# MCPS_Power_030307.net
KiCad netlist of a schematic drawn in Altium Designer
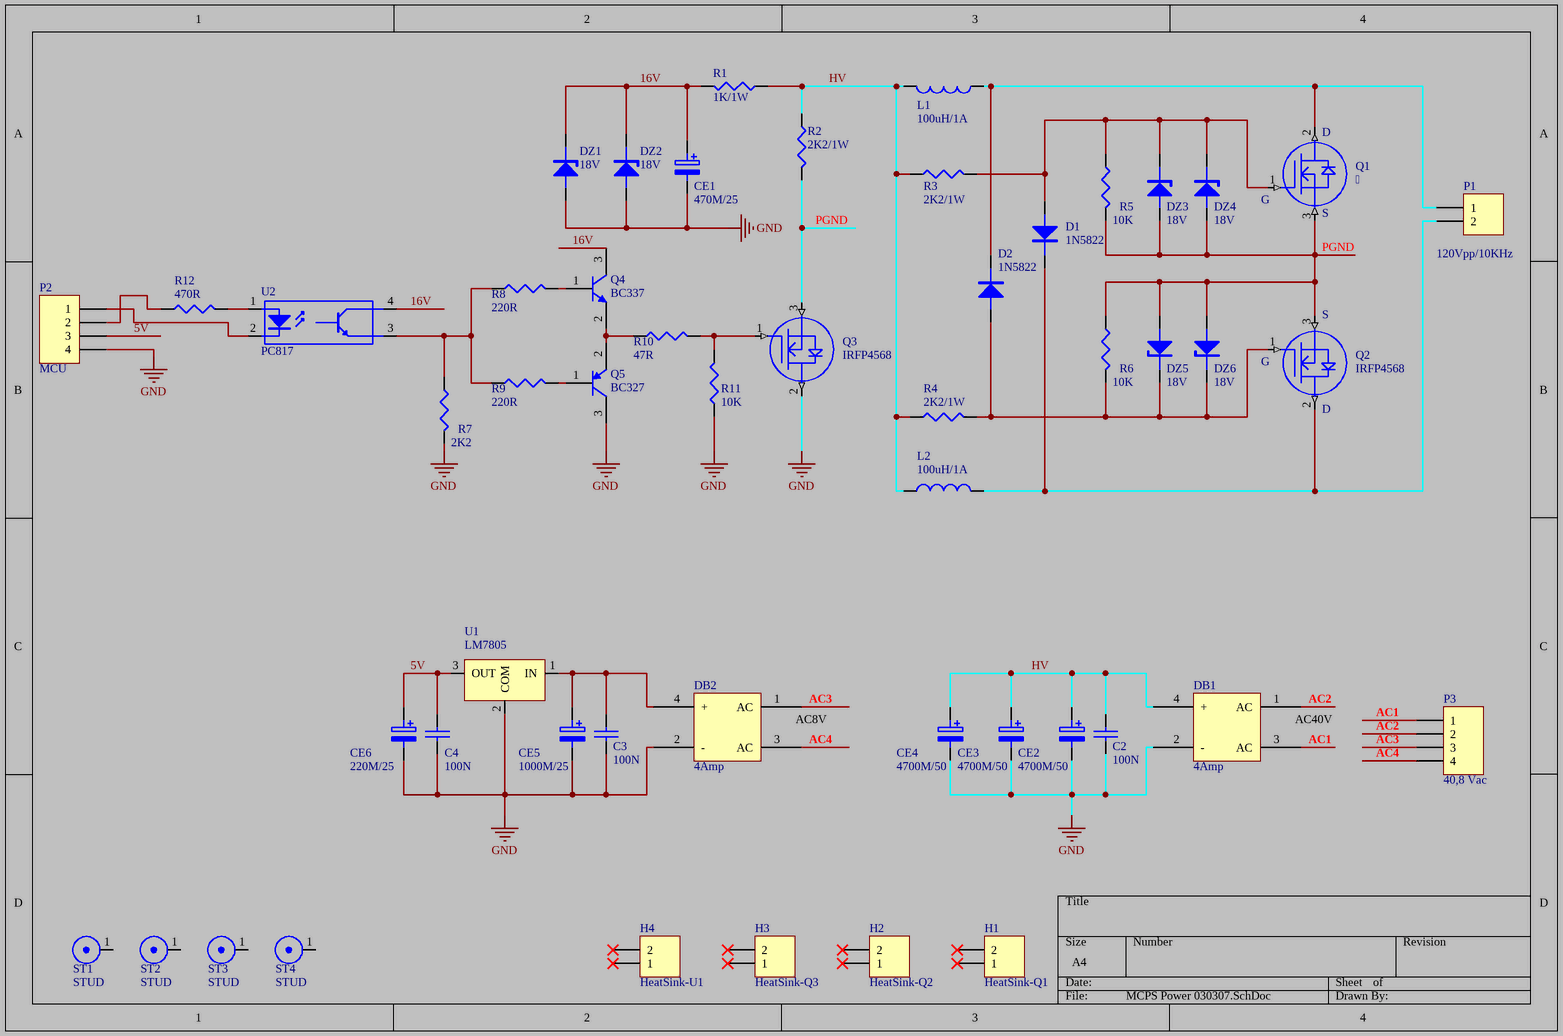
[diagram p0: MCPS Power 030307.SchDoc]

(export (version "E")
  (design (tool "Eeschema 10.0.6"))
  (components
    (comp (ref "C2") (value "100N") (footprint "c2P") (libsource (lib "*") (part "C")))
    (comp (ref "C3") (value "100N") (footprint "c2P") (libsource (lib "*") (part "C")))
    (comp (ref "C4") (value "100N") (footprint "c2P") (libsource (lib "*") (part "C")))
    (comp (ref "CE1") (value "470M/25") (footprint "cap2p12") (libsource (lib "*") (part "E")))
    (comp (ref "CE2") (value "4700M/50") (footprint "CAP3P5") (libsource (lib "*") (part "E")))
    (comp (ref "CE3") (value "4700M/50") (footprint "CAP3P5") (libsource (lib "*") (part "E")))
    (comp (ref "CE4") (value "4700M/50") (footprint "CAP3P5") (libsource (lib "*") (part "E")))
    (comp (ref "CE5") (value "1000M/25") (footprint "cap2p12") (libsource (lib "*") (part "E")))
    (comp (ref "CE6") (value "220M/25") (footprint "cap2p12") (libsource (lib "*") (part "E")))
    (comp (ref "D1") (value "1N5822") (footprint "D54") (libsource (lib "MyAltiumLib9702") (part "D")))
    (comp (ref "D2") (value "1N5822") (footprint "D54") (libsource (lib "MyAltiumLib9702") (part "D")))
    (comp (ref "DB1")
      (value "4Amp")
      (footprint "BRG GBU")
      (libsource (lib "1402 Schlib 2020") (part "BRIDGE"))
    )
    (comp (ref "DB2") (value "4Amp") (footprint "BRG F") (libsource (lib "1402 Schlib 2020") (part "BRIDGE")))
    (comp (ref "DZ1") (value "18V") (footprint "D4P") (libsource (lib "MyAltiumLib9702") (part "DZ")))
    (comp (ref "DZ2") (value "18V") (footprint "D4P") (libsource (lib "MyAltiumLib9702") (part "DZ")))
    (comp (ref "DZ3") (value "18V") (footprint "D4P") (libsource (lib "MyAltiumLib9702") (part "DZ")))
    (comp (ref "DZ4") (value "18V") (footprint "D4P") (libsource (lib "MyAltiumLib9702") (part "DZ")))
    (comp (ref "DZ5") (value "18V") (footprint "D4P") (libsource (lib "MyAltiumLib9702") (part "DZ")))
    (comp (ref "DZ6") (value "18V") (footprint "D4P") (libsource (lib "MyAltiumLib9702") (part "DZ")))
    (comp (ref "H1")
      (value "HeatSink-Q1")
      (footprint "heatsink2")
      (description "Header, 2-Pin")
      (fields (field (name "PUBLISHER") "Altium Limited"))
      (libsource (lib "") (part "Header 2_1"))
    )
    (comp (ref "H2")
      (value "HeatSink-Q2")
      (footprint "heatsink2")
      (description "Header, 2-Pin")
      (fields (field (name "PUBLISHER") "Altium Limited"))
      (libsource (lib "") (part "Header 2_1"))
    )
    (comp (ref "H3")
      (value "HeatSink-Q3")
      (footprint "heatsink2")
      (description "Header, 2-Pin")
      (fields (field (name "PUBLISHER") "Altium Limited"))
      (libsource (lib "") (part "Header 2_1"))
    )
    (comp (ref "H4")
      (value "HeatSink-U1")
      (footprint "heatsink5")
      (description "Header, 2-Pin")
      (fields (field (name "PUBLISHER") "Altium Limited"))
      (libsource (lib "") (part "Header 2_1"))
    )
    (comp (ref "L1")
      (value "100uH/1A")
      (footprint "Inductor-Brown")
      (libsource (lib "MyAltiumLib9702") (part "INDUCTOR"))
    )
    (comp (ref "L2") (value "100uH/1A") (footprint "Inductor-Brown") (libsource (lib "") (part "INDUCTOR_1")))
    (comp (ref "P1")
      (value "120Vpp/10KHz")
      (footprint "2EDG")
      (description "Header, 2-Pin")
      (fields (field (name "PUBLISHER") "Altium Limited"))
      (libsource (lib "Miscellaneous Connectors") (part "Header 2"))
    )
    (comp (ref "P2")
      (value "MCU")
      (footprint "DSIP4")
      (description "Header, 4-Pin")
      (fields (field (name "PUBLISHER") "Altium Limited"))
      (libsource (lib "Miscellaneous Connectors") (part "Header 4"))
    )
    (comp (ref "P3")
      (value "40,8 Vac")
      (footprint "4EDG")
      (description "Header, 4-Pin")
      (fields (field (name "PUBLISHER") "Altium Limited"))
      (libsource (lib "") (part "Header 4_1"))
    )
    (comp (ref "Q1") (value "") (footprint "TO220T") (libsource (lib "1402 Schlib 2020") (part "MOSFET N")))
    (comp (ref "Q2")
      (value "IRFP4568")
      (footprint "TO220T")
      (libsource (lib "1402 Schlib 2020") (part "MOSFET N"))
    )
    (comp (ref "Q3")
      (value "IRFP4568")
      (footprint "TO220T")
      (libsource (lib "1402 Schlib 2020") (part "MOSFET N"))
    )
    (comp (ref "Q4")
      (value "BC337")
      (footprint "CBE-BC546")
      (libsource (lib "1402 Schlib 2020") (part "BC546"))
    )
    (comp (ref "Q5")
      (value "BC327")
      (footprint "CBE-BC546")
      (description "PNP")
      (fields (field (name "PUBLISHER") "Altium Limited"))
      (libsource (lib "1402 Schlib 2020") (part "M6"))
    )
    (comp (ref "R1") (value "1K/1W") (footprint "w1") (libsource (lib "*") (part "R")))
    (comp (ref "R2") (value "2K2/1W") (footprint "w1") (libsource (lib "*") (part "R")))
    (comp (ref "R3") (value "2K2/1W") (footprint "w1") (libsource (lib "*") (part "R")))
    (comp (ref "R4") (value "2K2/1W") (footprint "w1") (libsource (lib "*") (part "R")))
    (comp (ref "R5") (value "10K") (footprint "R5P") (libsource (lib "*") (part "R")))
    (comp (ref "R6") (value "10K") (footprint "R5P") (libsource (lib "*") (part "R")))
    (comp (ref "R7") (value "2K2") (footprint "R4P") (libsource (lib "*") (part "R")))
    (comp (ref "R8") (value "220R") (footprint "R4P") (libsource (lib "*") (part "R")))
    (comp (ref "R9") (value "220R") (footprint "R4P") (libsource (lib "*") (part "R")))
    (comp (ref "R10") (value "47R") (footprint "R4P") (libsource (lib "*") (part "R")))
    (comp (ref "R11") (value "10K") (footprint "R4P") (libsource (lib "*") (part "R")))
    (comp (ref "R12") (value "470R") (footprint "R4P") (libsource (lib "*") (part "R")))
    (comp (ref "ST1") (value "STUD") (footprint "CORNER") (libsource (lib "1402 Schlib 2020") (part "STUD")))
    (comp (ref "ST2") (value "STUD") (footprint "CORNER") (libsource (lib "1402 Schlib 2020") (part "STUD")))
    (comp (ref "ST3") (value "STUD") (footprint "CORNER") (libsource (lib "1402 Schlib 2020") (part "STUD")))
    (comp (ref "ST4") (value "STUD") (footprint "CORNER") (libsource (lib "1402 Schlib 2020") (part "STUD")))
    (comp (ref "U1")
      (value "LM7805")
      (footprint "TO220T")
      (description "SMD")
      (libsource (lib "1402 Schlib 2020") (part "Regulator"))
    )
    (comp (ref "U2")
      (value "PC817")
      (footprint "DIP4")
      (libsource (lib "1402 Schlib 2020") (part "OPTODIP4"))
    )
  )
  (nets
    (net (code "1") (name "/5V") (class "Default")
      (node (ref "C4") (pin "1") (pintype "passive"))
      (node (ref "CE6") (pin "1") (pintype "passive"))
      (node (ref "P2") (pin "3") (pinfunction "3_3") (pintype "passive"))
      (node (ref "U1") (pin "3") (pinfunction "OUT_3") (pintype "passive"))
    )
    (net (code "2") (name "/16V") (class "Default")
      (node (ref "CE1") (pin "1") (pintype "passive"))
      (node (ref "DZ1") (pin "2") (pinfunction "K_2") (pintype "passive"))
      (node (ref "DZ2") (pin "2") (pinfunction "K_2") (pintype "passive"))
      (node (ref "Q4") (pin "3") (pinfunction "C_3") (pintype "passive"))
      (node (ref "R1") (pin "2") (pintype "passive"))
      (node (ref "U2") (pin "4") (pinfunction "C_4") (pintype "passive"))
    )
    (net (code "3") (name "/AC1") (class "Default")
      (node (ref "DB1") (pin "3") (pinfunction "AC_3") (pintype "passive"))
      (node (ref "P3") (pin "1") (pinfunction "1_1") (pintype "passive"))
    )
    (net (code "4") (name "/AC2") (class "Default")
      (node (ref "DB1") (pin "1") (pinfunction "AC_1") (pintype "passive"))
      (node (ref "P3") (pin "2") (pinfunction "2_2") (pintype "passive"))
    )
    (net (code "5") (name "/AC3") (class "Default")
      (node (ref "DB2") (pin "1") (pinfunction "AC_1") (pintype "passive"))
      (node (ref "P3") (pin "3") (pinfunction "3_3") (pintype "passive"))
    )
    (net (code "6") (name "/AC4") (class "Default")
      (node (ref "DB2") (pin "3") (pinfunction "AC_3") (pintype "passive"))
      (node (ref "P3") (pin "4") (pinfunction "4_4") (pintype "passive"))
    )
    (net (code "7") (name "/HV") (class "Default")
      (node (ref "C2") (pin "1") (pintype "passive"))
      (node (ref "CE2") (pin "1") (pintype "passive"))
      (node (ref "CE3") (pin "1") (pintype "passive"))
      (node (ref "CE4") (pin "1") (pintype "passive"))
      (node (ref "DB1") (pin "4") (pinfunction "+_4") (pintype "passive"))
      (node (ref "L1") (pin "1") (pinfunction "1_1") (pintype "passive"))
      (node (ref "L2") (pin "1") (pinfunction "1_1") (pintype "passive"))
      (node (ref "R1") (pin "1") (pintype "passive"))
      (node (ref "R2") (pin "1") (pintype "passive"))
      (node (ref "R3") (pin "1") (pintype "passive"))
      (node (ref "R4") (pin "1") (pintype "passive"))
    )
    (net (code "8") (name "/PGND") (class "Default")
      (node (ref "DZ3") (pin "1") (pinfunction "A_1") (pintype "passive"))
      (node (ref "DZ4") (pin "1") (pinfunction "A_1") (pintype "passive"))
      (node (ref "DZ5") (pin "1") (pinfunction "A_1") (pintype "passive"))
      (node (ref "DZ6") (pin "1") (pinfunction "A_1") (pintype "passive"))
      (node (ref "Q1") (pin "3") (pinfunction "S_3") (pintype "input"))
      (node (ref "Q2") (pin "3") (pinfunction "S_3") (pintype "input"))
      (node (ref "Q3") (pin "3") (pinfunction "S_3") (pintype "input"))
      (node (ref "R2") (pin "2") (pintype "passive"))
      (node (ref "R5") (pin "2") (pintype "passive"))
      (node (ref "R6") (pin "1") (pintype "passive"))
    )
    (net (code "9") (name "GND") (class "Default")
      (node (ref "C2") (pin "2") (pintype "passive"))
      (node (ref "C3") (pin "2") (pintype "passive"))
      (node (ref "C4") (pin "2") (pintype "passive"))
      (node (ref "CE1") (pin "2") (pintype "passive"))
      (node (ref "CE2") (pin "2") (pintype "passive"))
      (node (ref "CE3") (pin "2") (pintype "passive"))
      (node (ref "CE4") (pin "2") (pintype "passive"))
      (node (ref "CE5") (pin "2") (pintype "passive"))
      (node (ref "CE6") (pin "2") (pintype "passive"))
      (node (ref "DB1") (pin "2") (pinfunction "-_2") (pintype "passive"))
      (node (ref "DB2") (pin "2") (pinfunction "-_2") (pintype "passive"))
      (node (ref "DZ1") (pin "1") (pinfunction "A_1") (pintype "passive"))
      (node (ref "DZ2") (pin "1") (pinfunction "A_1") (pintype "passive"))
      (node (ref "P2") (pin "4") (pinfunction "4_4") (pintype "passive"))
      (node (ref "Q3") (pin "2") (pinfunction "D_2") (pintype "output"))
      (node (ref "Q5") (pin "3") (pinfunction "C_3") (pintype "passive"))
      (node (ref "R11") (pin "1") (pintype "passive"))
      (node (ref "R7") (pin "2") (pintype "passive"))
      (node (ref "U1") (pin "2") (pinfunction "COM_2") (pintype "passive"))
    )
    (net (code "10") (name "Net-(D1-A)") (class "Default")
      (node (ref "D1") (pin "1") (pinfunction "A_1") (pintype "passive"))
      (node (ref "DZ3") (pin "2") (pinfunction "K_2") (pintype "passive"))
      (node (ref "DZ4") (pin "2") (pinfunction "K_2") (pintype "passive"))
      (node (ref "Q1") (pin "1") (pinfunction "G_1") (pintype "input"))
      (node (ref "R3") (pin "2") (pintype "passive"))
      (node (ref "R5") (pin "1") (pintype "passive"))
    )
    (net (code "11") (name "Net-(D1-K)") (class "Default")
      (node (ref "D1") (pin "2") (pinfunction "K_2") (pintype "passive"))
      (node (ref "L2") (pin "2") (pinfunction "2_2") (pintype "passive"))
      (node (ref "P1") (pin "2") (pinfunction "2_2") (pintype "passive"))
      (node (ref "Q2") (pin "2") (pinfunction "D_2") (pintype "output"))
    )
    (net (code "12") (name "Net-(D2-A)") (class "Default")
      (node (ref "D2") (pin "1") (pinfunction "A_1") (pintype "passive"))
      (node (ref "DZ5") (pin "2") (pinfunction "K_2") (pintype "passive"))
      (node (ref "DZ6") (pin "2") (pinfunction "K_2") (pintype "passive"))
      (node (ref "Q2") (pin "1") (pinfunction "G_1") (pintype "input"))
      (node (ref "R4") (pin "2") (pintype "passive"))
      (node (ref "R6") (pin "2") (pintype "passive"))
    )
    (net (code "13") (name "Net-(D2-K)") (class "Default")
      (node (ref "D2") (pin "2") (pinfunction "K_2") (pintype "passive"))
      (node (ref "L1") (pin "2") (pinfunction "2_2") (pintype "passive"))
      (node (ref "P1") (pin "1") (pinfunction "1_1") (pintype "passive"))
      (node (ref "Q1") (pin "2") (pinfunction "D_2") (pintype "output"))
    )
    (net (code "14") (name "Net-(DB2-+)") (class "Default")
      (node (ref "C3") (pin "1") (pintype "passive"))
      (node (ref "CE5") (pin "1") (pintype "passive"))
      (node (ref "DB2") (pin "4") (pinfunction "+_4") (pintype "passive"))
      (node (ref "U1") (pin "1") (pinfunction "IN_1") (pintype "passive"))
    )
    (net (code "15") (name "Net-(P2-Pad2)") (class "Default")
      (node (ref "P2") (pin "2") (pinfunction "2_2") (pintype "passive"))
      (node (ref "R12") (pin "1") (pintype "passive"))
    )
    (net (code "16") (name "Net-(Q3-G)") (class "Default")
      (node (ref "Q3") (pin "1") (pinfunction "G_1") (pintype "input"))
      (node (ref "R10") (pin "2") (pintype "passive"))
      (node (ref "R11") (pin "2") (pintype "passive"))
    )
    (net (code "17") (name "Net-(Q4-B)") (class "Default")
      (node (ref "Q4") (pin "1") (pinfunction "B_1") (pintype "passive"))
      (node (ref "R8") (pin "2") (pintype "passive"))
    )
    (net (code "18") (name "Net-(Q4-E)") (class "Default")
      (node (ref "Q4") (pin "2") (pinfunction "E_2") (pintype "passive"))
      (node (ref "Q5") (pin "2") (pinfunction "B_2") (pintype "passive"))
      (node (ref "R10") (pin "1") (pintype "passive"))
    )
    (net (code "19") (name "Net-(Q5-E)") (class "Default")
      (node (ref "Q5") (pin "1") (pinfunction "E_1") (pintype "passive"))
      (node (ref "R9") (pin "2") (pintype "passive"))
    )
    (net (code "20") (name "Net-(U2-A)") (class "Default")
      (node (ref "R12") (pin "2") (pintype "passive"))
      (node (ref "U2") (pin "1") (pinfunction "A_1") (pintype "passive"))
    )
    (net (code "21") (name "Net-(U2-E)") (class "Default")
      (node (ref "R7") (pin "1") (pintype "passive"))
      (node (ref "R8") (pin "1") (pintype "passive"))
      (node (ref "R9") (pin "1") (pintype "passive"))
      (node (ref "U2") (pin "3") (pinfunction "E_3") (pintype "passive"))
    )
    (net (code "22") (name "Net-(U2-K)") (class "Default")
      (node (ref "P2") (pin "1") (pinfunction "1_1") (pintype "passive"))
      (node (ref "U2") (pin "2") (pinfunction "K_2") (pintype "passive"))
    )
    (net (code "23") (name "unconnected-(H1-Pad1)") (class "Default")
      (node (ref "H1") (pin "1") (pinfunction "1_1") (pintype "passive+no_connect"))
    )
    (net (code "24") (name "unconnected-(H1-Pad2)") (class "Default")
      (node (ref "H1") (pin "2") (pinfunction "2_2") (pintype "passive+no_connect"))
    )
    (net (code "25") (name "unconnected-(H2-Pad1)") (class "Default")
      (node (ref "H2") (pin "1") (pinfunction "1_1") (pintype "passive+no_connect"))
    )
    (net (code "26") (name "unconnected-(H2-Pad2)") (class "Default")
      (node (ref "H2") (pin "2") (pinfunction "2_2") (pintype "passive+no_connect"))
    )
    (net (code "27") (name "unconnected-(H3-Pad1)") (class "Default")
      (node (ref "H3") (pin "1") (pinfunction "1_1") (pintype "passive+no_connect"))
    )
    (net (code "28") (name "unconnected-(H3-Pad2)") (class "Default")
      (node (ref "H3") (pin "2") (pinfunction "2_2") (pintype "passive+no_connect"))
    )
    (net (code "29") (name "unconnected-(H4-Pad1)") (class "Default")
      (node (ref "H4") (pin "1") (pinfunction "1_1") (pintype "passive+no_connect"))
    )
    (net (code "30") (name "unconnected-(H4-Pad2)") (class "Default")
      (node (ref "H4") (pin "2") (pinfunction "2_2") (pintype "passive+no_connect"))
    )
    (net (code "31") (name "unconnected-(ST1-Pad1)") (class "Default")
      (node (ref "ST1") (pin "1") (pintype "passive"))
    )
    (net (code "32") (name "unconnected-(ST2-Pad1)") (class "Default")
      (node (ref "ST2") (pin "1") (pintype "passive"))
    )
    (net (code "33") (name "unconnected-(ST3-Pad1)") (class "Default")
      (node (ref "ST3") (pin "1") (pintype "passive"))
    )
    (net (code "34") (name "unconnected-(ST4-Pad1)") (class "Default")
      (node (ref "ST4") (pin "1") (pintype "passive"))
    )
  )
)
